# Triple.net
KiCad netlist of a schematic drawn in EAGLE
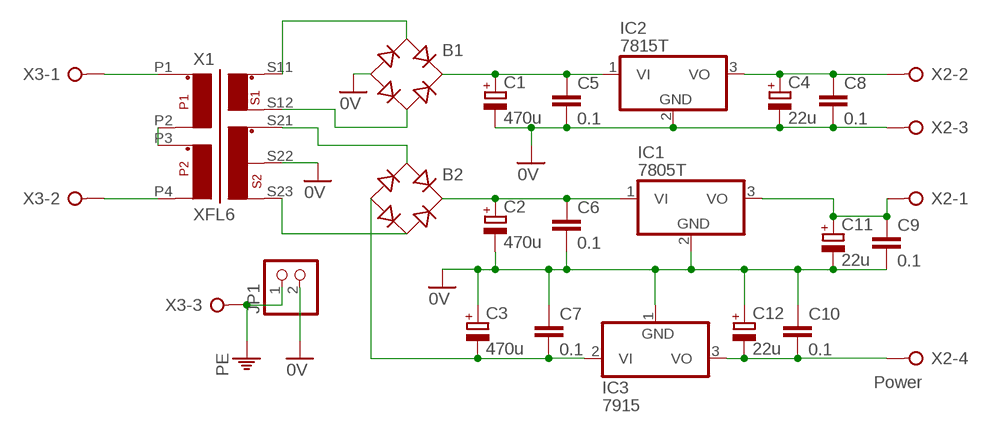
[diagram p0: schematic, sheet 1]

(export (version "E")
  (design (tool "Eeschema 10.0.6"))
  (components
    (comp (ref "B1")
      (value "RB1A")
      (footprint "eagle-import:RB1A")
      (libsource (lib "eagle-import") (part "RB1A"))
    )
    (comp (ref "B2")
      (value "RB1A")
      (footprint "eagle-import:RB1A")
      (libsource (lib "eagle-import") (part "RB1A"))
    )
    (comp (ref "C1")
      (value "470u")
      (footprint "eagle-import:E5-10,5")
      (libsource (lib "eagle-import") (part "CPOL-EUE5-10.5"))
    )
    (comp (ref "C2")
      (value "470u")
      (footprint "eagle-import:E5-10,5")
      (libsource (lib "eagle-import") (part "CPOL-EUE5-10.5"))
    )
    (comp (ref "C3")
      (value "470u")
      (footprint "eagle-import:E5-10,5")
      (libsource (lib "eagle-import") (part "CPOL-EUE5-10.5"))
    )
    (comp (ref "C4")
      (value "22u")
      (footprint "eagle-import:E5-10,5")
      (libsource (lib "eagle-import") (part "CPOL-EUE5-10.5"))
    )
    (comp (ref "C5")
      (value "0.1")
      (footprint "eagle-import:C050-025X075")
      (libsource (lib "eagle-import") (part "C-EU050-025X075"))
    )
    (comp (ref "C6")
      (value "0.1")
      (footprint "eagle-import:C050-025X075")
      (libsource (lib "eagle-import") (part "C-EU050-025X075"))
    )
    (comp (ref "C7")
      (value "0.1")
      (footprint "eagle-import:C050-025X075")
      (libsource (lib "eagle-import") (part "C-EU050-025X075"))
    )
    (comp (ref "C8")
      (value "0.1")
      (footprint "eagle-import:C050-025X075")
      (libsource (lib "eagle-import") (part "C-EU050-025X075"))
    )
    (comp (ref "C9")
      (value "0.1")
      (footprint "eagle-import:C050-025X075")
      (libsource (lib "eagle-import") (part "C-EU050-025X075"))
    )
    (comp (ref "C10")
      (value "0.1")
      (footprint "eagle-import:C050-025X075")
      (libsource (lib "eagle-import") (part "C-EU050-025X075"))
    )
    (comp (ref "C11")
      (value "22u")
      (footprint "eagle-import:E5-10,5")
      (libsource (lib "eagle-import") (part "CPOL-EUE5-10.5"))
    )
    (comp (ref "C12")
      (value "22u")
      (footprint "eagle-import:E5-10,5")
      (libsource (lib "eagle-import") (part "CPOL-EUE5-10.5"))
    )
    (comp (ref "IC1")
      (value "7805T")
      (footprint "eagle-import:TO220H")
      (libsource (lib "eagle-import") (part "78T05"))
    )
    (comp (ref "IC2")
      (value "7815T")
      (footprint "eagle-import:TO220H")
      (libsource (lib "eagle-import") (part "78T15"))
    )
    (comp (ref "IC3")
      (value "7915")
      (footprint "eagle-import:TO220H")
      (libsource (lib "eagle-import") (part "79T15"))
    )
    (comp (ref "JP1")
      (value "PINHD-1X2")
      (footprint "eagle-import:1X02")
      (libsource (lib "eagle-import") (part "PINHD-1X2"))
    )
    (comp (ref "X1")
      (value "XFL6")
      (footprint "eagle-import:FL6")
      (libsource (lib "eagle-import") (part "XFL6"))
    )
    (comp (ref "X2")
      (value "Power")
      (footprint "eagle-import:W237-4P")
      (libsource (lib "eagle-import") (part "W237-04P"))
    )
    (comp (ref "X3")
      (value "W237-03P")
      (footprint "eagle-import:W237-133")
      (libsource (lib "eagle-import") (part "W237-03P"))
    )
  )
  (nets
    (net (code "1") (name "0V") (class "Default")
      (node (ref "B1") (pin "-") (pinfunction "-_-") (pintype "passive"))
      (node (ref "C1") (pin "-") (pinfunction "-_-") (pintype "passive"))
      (node (ref "C10") (pin "1") (pinfunction "1_1") (pintype "passive"))
      (node (ref "C11") (pin "-") (pinfunction "-_-") (pintype "passive"))
      (node (ref "C12") (pin "+") (pinfunction "+_+") (pintype "passive"))
      (node (ref "C2") (pin "-") (pinfunction "-_-") (pintype "passive"))
      (node (ref "C3") (pin "+") (pinfunction "+_+") (pintype "passive"))
      (node (ref "C4") (pin "-") (pinfunction "-_-") (pintype "passive"))
      (node (ref "C5") (pin "2") (pinfunction "2_2") (pintype "passive"))
      (node (ref "C6") (pin "2") (pinfunction "2_2") (pintype "passive"))
      (node (ref "C7") (pin "1") (pinfunction "1_1") (pintype "passive"))
      (node (ref "C8") (pin "2") (pinfunction "2_2") (pintype "passive"))
      (node (ref "C9") (pin "2") (pinfunction "2_2") (pintype "passive"))
      (node (ref "IC1") (pin "2") (pinfunction "GND_2") (pintype "passive"))
      (node (ref "IC2") (pin "2") (pinfunction "GND_2") (pintype "passive"))
      (node (ref "IC3") (pin "1") (pinfunction "GND_1") (pintype "passive"))
      (node (ref "JP1") (pin "2") (pinfunction "2_2") (pintype "passive"))
      (node (ref "X1") (pin "S22") (pinfunction "S22_S22") (pintype "passive"))
      (node (ref "X2") (pin "3") (pinfunction "KL_3") (pintype "passive"))
    )
    (net (code "2") (name "Net-(B1-PadAC1)") (class "Default")
      (node (ref "B1") (pin "AC1") (pinfunction "AC1_AC1") (pintype "passive"))
      (node (ref "X1") (pin "S11") (pinfunction "S11_S11") (pintype "passive"))
    )
    (net (code "3") (name "Net-(B1-PadAC2)") (class "Default")
      (node (ref "B1") (pin "AC2") (pinfunction "AC2_AC2") (pintype "passive"))
      (node (ref "X1") (pin "S12") (pinfunction "S12_S12") (pintype "passive"))
    )
    (net (code "4") (name "Net-(B2-PadAC1)") (class "Default")
      (node (ref "B2") (pin "AC1") (pinfunction "AC1_AC1") (pintype "passive"))
      (node (ref "X1") (pin "S21") (pinfunction "S21_S21") (pintype "passive"))
    )
    (net (code "5") (name "Net-(B2-PadAC2)") (class "Default")
      (node (ref "B2") (pin "AC2") (pinfunction "AC2_AC2") (pintype "passive"))
      (node (ref "X1") (pin "S23") (pinfunction "S23_S23") (pintype "passive"))
    )
    (net (code "6") (name "Net-(IC1-VI)") (class "Default")
      (node (ref "B2") (pin "+") (pinfunction "+_+") (pintype "passive"))
      (node (ref "C2") (pin "+") (pinfunction "+_+") (pintype "passive"))
      (node (ref "C6") (pin "1") (pinfunction "1_1") (pintype "passive"))
      (node (ref "IC1") (pin "1") (pinfunction "VI_1") (pintype "input"))
    )
    (net (code "7") (name "Net-(IC1-VO)") (class "Default")
      (node (ref "C11") (pin "+") (pinfunction "+_+") (pintype "passive"))
      (node (ref "C9") (pin "1") (pinfunction "1_1") (pintype "passive"))
      (node (ref "IC1") (pin "3") (pinfunction "VO_3") (pintype "passive"))
      (node (ref "X2") (pin "1") (pinfunction "KL_1") (pintype "passive"))
    )
    (net (code "8") (name "Net-(IC2-VI)") (class "Default")
      (node (ref "B1") (pin "+") (pinfunction "+_+") (pintype "passive"))
      (node (ref "C1") (pin "+") (pinfunction "+_+") (pintype "passive"))
      (node (ref "C5") (pin "1") (pinfunction "1_1") (pintype "passive"))
      (node (ref "IC2") (pin "1") (pinfunction "VI_1") (pintype "input"))
    )
    (net (code "9") (name "Net-(IC2-VO)") (class "Default")
      (node (ref "C4") (pin "+") (pinfunction "+_+") (pintype "passive"))
      (node (ref "C8") (pin "1") (pinfunction "1_1") (pintype "passive"))
      (node (ref "IC2") (pin "3") (pinfunction "VO_3") (pintype "passive"))
      (node (ref "X2") (pin "2") (pinfunction "KL_2") (pintype "passive"))
    )
    (net (code "10") (name "Net-(IC3-VI)") (class "Default")
      (node (ref "B2") (pin "-") (pinfunction "-_-") (pintype "passive"))
      (node (ref "C3") (pin "-") (pinfunction "-_-") (pintype "passive"))
      (node (ref "C7") (pin "2") (pinfunction "2_2") (pintype "passive"))
      (node (ref "IC3") (pin "2") (pinfunction "VI_2") (pintype "input"))
    )
    (net (code "11") (name "Net-(IC3-VO)") (class "Default")
      (node (ref "C10") (pin "2") (pinfunction "2_2") (pintype "passive"))
      (node (ref "C12") (pin "-") (pinfunction "-_-") (pintype "passive"))
      (node (ref "IC3") (pin "3") (pinfunction "VO_3") (pintype "passive"))
      (node (ref "X2") (pin "4") (pinfunction "KL_4") (pintype "passive"))
    )
    (net (code "12") (name "Net-(X1-PadP2)") (class "Default")
      (node (ref "X1") (pin "P2") (pinfunction "P2_P2") (pintype "passive"))
      (node (ref "X1") (pin "P3") (pinfunction "P3_P3") (pintype "passive"))
    )
    (net (code "13") (name "Net-(X3A-KL)") (class "Default")
      (node (ref "X1") (pin "P1") (pinfunction "P1_P1") (pintype "passive"))
      (node (ref "X3") (pin "1") (pinfunction "KL_1") (pintype "passive"))
    )
    (net (code "14") (name "Net-(X3B-KL)") (class "Default")
      (node (ref "X1") (pin "P4") (pinfunction "P4_P4") (pintype "passive"))
      (node (ref "X3") (pin "2") (pinfunction "KL_2") (pintype "passive"))
    )
    (net (code "15") (name "PE") (class "Default")
      (node (ref "JP1") (pin "1") (pinfunction "1_1") (pintype "passive"))
      (node (ref "X3") (pin "3") (pinfunction "KL_3") (pintype "passive"))
    )
  )
)
